# RAFT_DuckLink_3V3_Reg.net
KiCad netlist of a schematic drawn in EAGLE
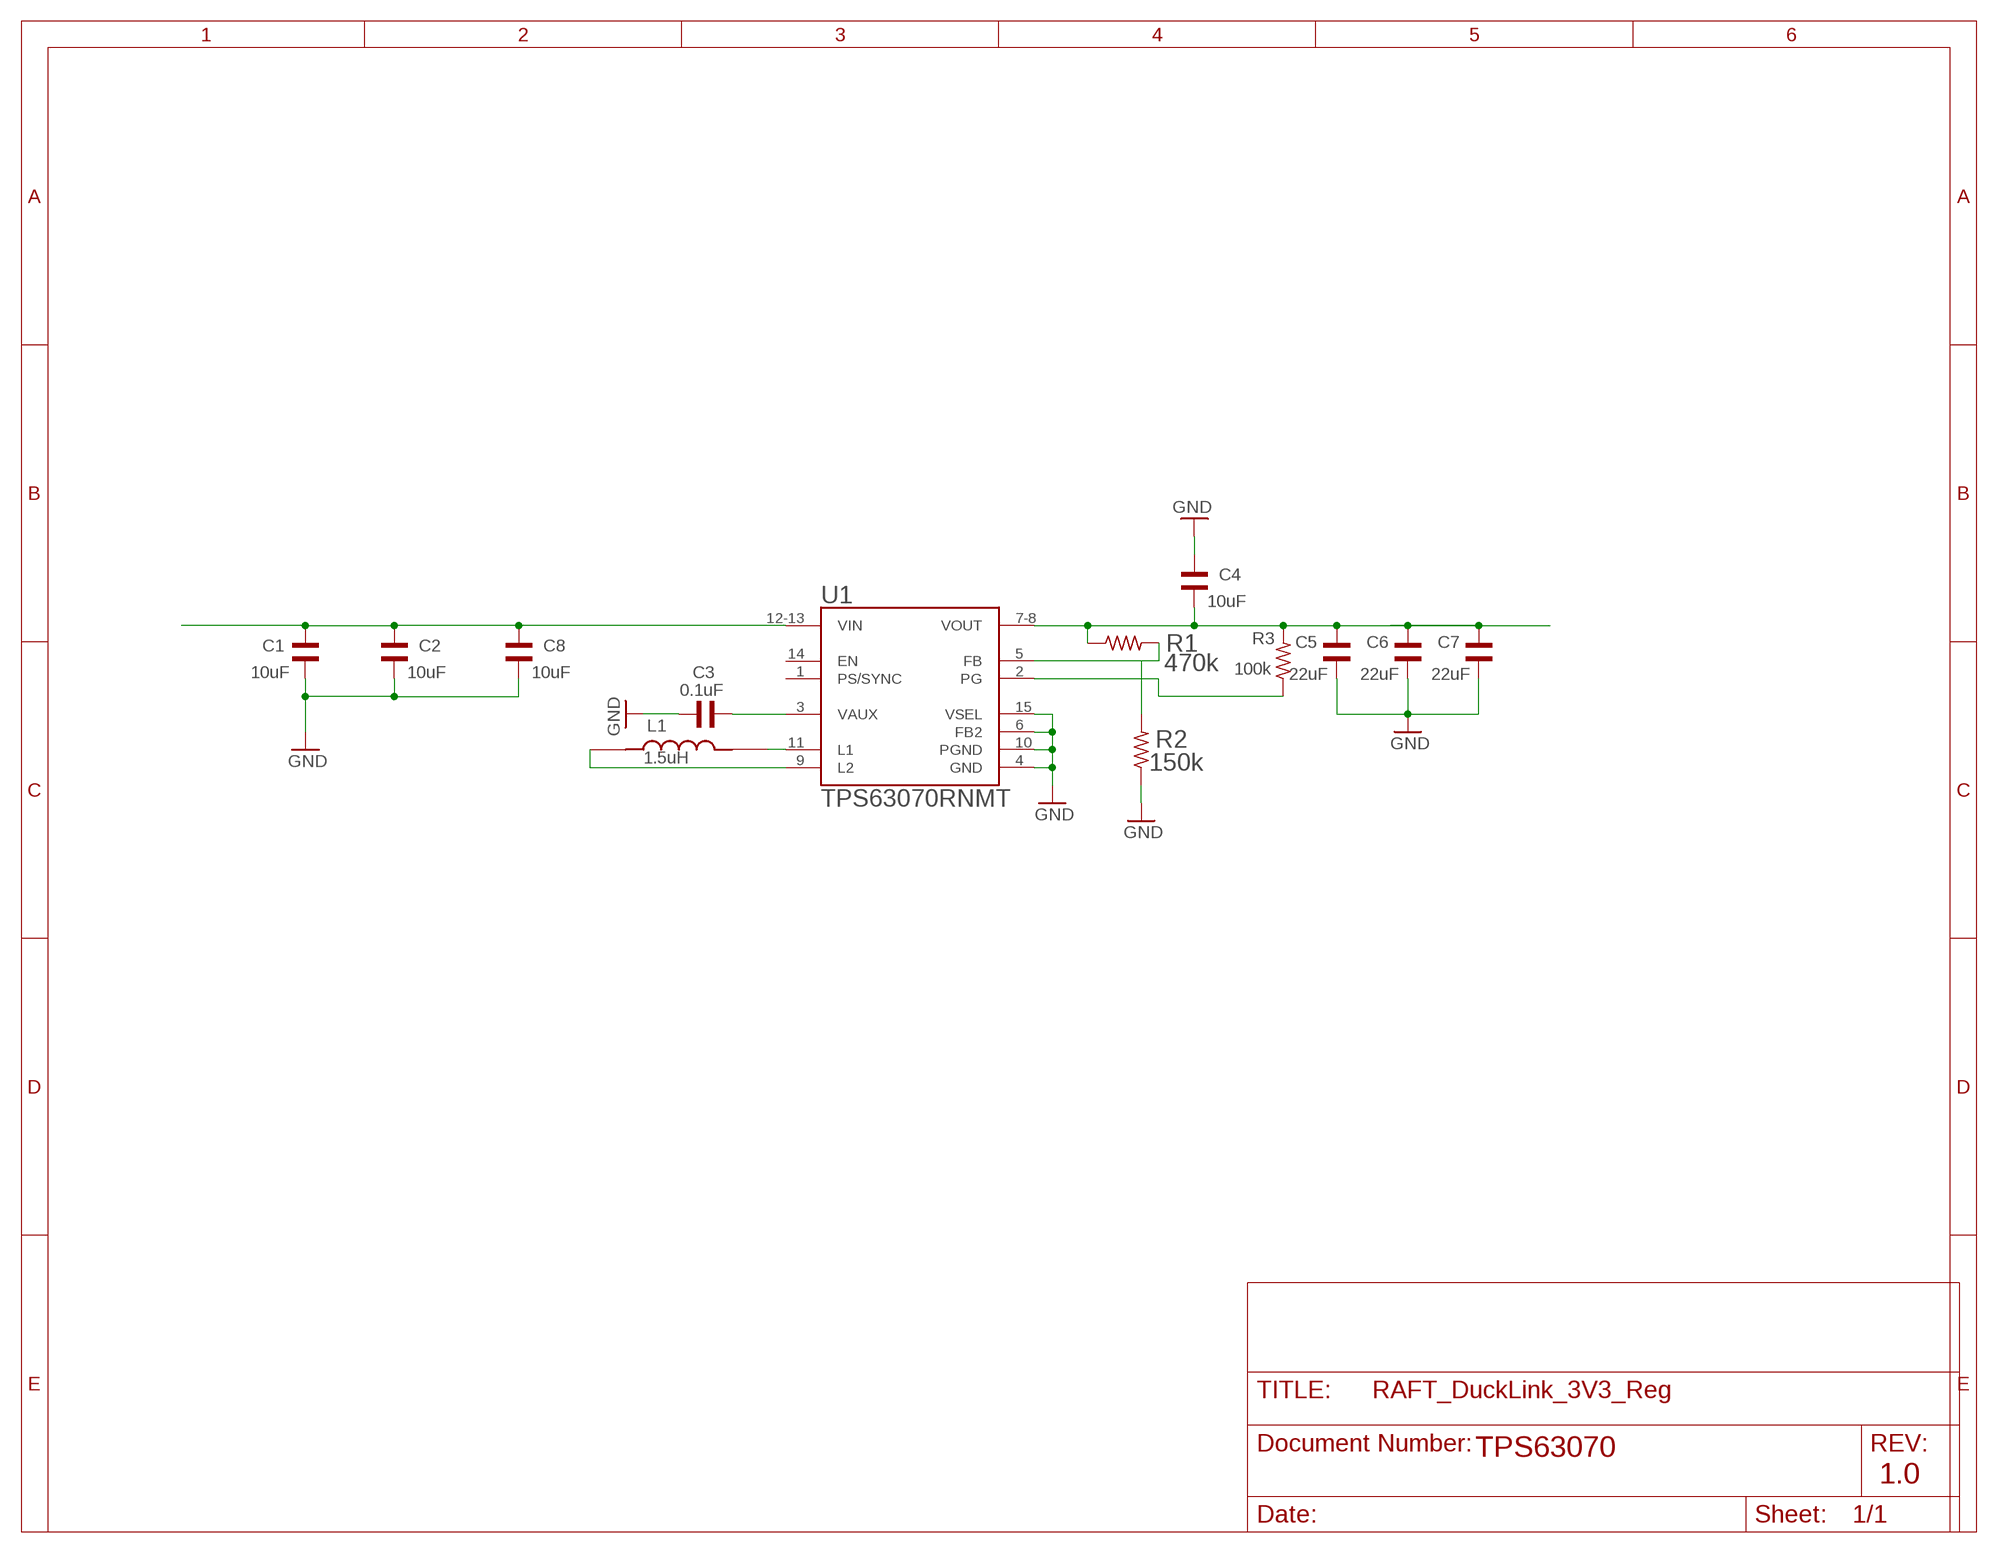
[diagram p0: schematic, sheet 1]

(export (version "E")
  (design (tool "Eeschema 10.0.6"))
  (components
    (comp (ref "C1")
      (value "10uF")
      (footprint "eagle-import:CAPC1005X70N")
      (fields (field (name "MF") "Murata Electronics") (field (name "MP") "GRM155C80J106ME11D"))
      (libsource (lib "eagle-import") (part "GRM155C80J106ME11D"))
    )
    (comp (ref "C2")
      (value "10uF")
      (footprint "eagle-import:CAPC1005X70N")
      (fields (field (name "MF") "Murata Electronics") (field (name "MP") "GRM155C80J106ME11D"))
      (libsource (lib "eagle-import") (part "GRM155C80J106ME11D"))
    )
    (comp (ref "C3")
      (value "0.1uF")
      (footprint "eagle-import:CAPC1005X55N")
      (fields (field (name "MF") "Murata") (field (name "MP") "GRM155R71C104KA88D"))
      (libsource (lib "eagle-import") (part "GRM155R71C104KA88D"))
    )
    (comp (ref "C4")
      (value "10uF")
      (footprint "eagle-import:CAPC1005X70N")
      (fields (field (name "MF") "Murata Electronics") (field (name "MP") "GRM155C80J106ME11D"))
      (libsource (lib "eagle-import") (part "GRM155C80J106ME11D"))
    )
    (comp (ref "C5")
      (value "22uF")
      (footprint "eagle-import:CAPC1005X55N")
      (fields
        (field (name "DIGI-KEY_PART_NUMBER") "1276-7090-1-ND")
        (field (name "MF") "Samsung Electro-Mechanics")
        (field (name "MP") "CL05A226MQ5N6J8")
      )
      (libsource (lib "eagle-import") (part "CL05A226MQ5N6J8"))
    )
    (comp (ref "C6")
      (value "22uF")
      (footprint "eagle-import:CAPC1005X55N")
      (fields
        (field (name "DIGI-KEY_PART_NUMBER") "1276-7090-1-ND")
        (field (name "MF") "Samsung Electro-Mechanics")
        (field (name "MP") "CL05A226MQ5N6J8")
      )
      (libsource (lib "eagle-import") (part "CL05A226MQ5N6J8"))
    )
    (comp (ref "C7")
      (value "22uF")
      (footprint "eagle-import:CAPC1005X55N")
      (fields
        (field (name "DIGI-KEY_PART_NUMBER") "1276-7090-1-ND")
        (field (name "MF") "Samsung Electro-Mechanics")
        (field (name "MP") "CL05A226MQ5N6J8")
      )
      (libsource (lib "eagle-import") (part "CL05A226MQ5N6J8"))
    )
    (comp (ref "C8")
      (value "10uF")
      (footprint "eagle-import:CAPC1005X70N")
      (fields (field (name "MF") "Murata Electronics") (field (name "MP") "GRM155C80J106ME11D"))
      (libsource (lib "eagle-import") (part "GRM155C80J106ME11D"))
    )
    (comp (ref "L1")
      (value "1.5uH")
      (footprint "eagle-import:IND_XFL4020-152MEB")
      (fields (field (name "MF") "Coilcraft") (field (name "MP") "XFL4020-152MEB"))
      (libsource (lib "eagle-import") (part "XFL4020-152MEB"))
    )
    (comp (ref "R1")
      (value "470k")
      (footprint "eagle-import:RESC1005X40N")
      (fields (field (name "MF") "Panasonic") (field (name "MP") "ERJ-PA2F4703X"))
      (libsource (lib "eagle-import") (part "ERJ-PA2F4703X"))
    )
    (comp (ref "R2")
      (value "150k")
      (footprint "eagle-import:RESC1005X40N")
      (fields (field (name "MF") "Panasonic Electronic") (field (name "MP") "ERJ-2GEJ154X"))
      (libsource (lib "eagle-import") (part "ERJ-2GEJ154X"))
    )
    (comp (ref "R3")
      (value "100k")
      (footprint "eagle-import:RESC1005X40N")
      (libsource (lib "eagle-import") (part "CRCW0402100KFKED"))
    )
    (comp (ref "U1")
      (value "TPS63070RNMT")
      (footprint "eagle-import:QFN50P250X300X100-15N")
      (fields (field (name "MF") "Texas Instruments"))
      (libsource (lib "eagle-import") (part "TPS63070RNMT"))
    )
  )
  (nets
    (net (code "1") (name "GND") (class "Default")
      (node (ref "C1") (pin "1") (pinfunction "1_1") (pintype "passive"))
      (node (ref "C2") (pin "1") (pinfunction "1_1") (pintype "passive"))
      (node (ref "C3") (pin "1") (pinfunction "1_1") (pintype "passive"))
      (node (ref "C4") (pin "2") (pinfunction "2_2") (pintype "passive"))
      (node (ref "C5") (pin "1") (pinfunction "1_1") (pintype "passive"))
      (node (ref "C6") (pin "1") (pinfunction "1_1") (pintype "passive"))
      (node (ref "C7") (pin "1") (pinfunction "1_1") (pintype "passive"))
      (node (ref "C8") (pin "1") (pinfunction "1_1") (pintype "passive"))
      (node (ref "R2") (pin "1") (pinfunction "1_1") (pintype "passive"))
      (node (ref "U1") (pin "10") (pinfunction "PGND_10") (pintype "power_in"))
      (node (ref "U1") (pin "15") (pinfunction "VSEL_15") (pintype "input"))
      (node (ref "U1") (pin "4") (pinfunction "GND_4") (pintype "power_in"))
      (node (ref "U1") (pin "6") (pinfunction "FB2_6") (pintype "output"))
    )
    (net (code "2") (name "Net-(U1-FB)") (class "Default")
      (node (ref "R1") (pin "2") (pinfunction "2_2") (pintype "passive"))
      (node (ref "R2") (pin "2") (pinfunction "2_2") (pintype "passive"))
      (node (ref "U1") (pin "5") (pinfunction "FB_5") (pintype "input"))
    )
    (net (code "3") (name "Net-(U1-L1)") (class "Default")
      (node (ref "L1") (pin "2") (pinfunction "2_2") (pintype "passive"))
      (node (ref "U1") (pin "11") (pinfunction "L1_11") (pintype "input"))
    )
    (net (code "4") (name "Net-(U1-L2)") (class "Default")
      (node (ref "L1") (pin "1") (pinfunction "1_1") (pintype "passive"))
      (node (ref "U1") (pin "9") (pinfunction "L2_9") (pintype "input"))
    )
    (net (code "5") (name "Net-(U1-PG)") (class "Default")
      (node (ref "R3") (pin "1") (pinfunction "1_1") (pintype "passive"))
      (node (ref "U1") (pin "2") (pinfunction "PG_2") (pintype "output"))
    )
    (net (code "6") (name "Net-(U1-VAUX)") (class "Default")
      (node (ref "C3") (pin "2") (pinfunction "2_2") (pintype "passive"))
      (node (ref "U1") (pin "3") (pinfunction "VAUX_3") (pintype "output"))
    )
    (net (code "7") (name "Net-(U1-VIN)") (class "Default")
      (node (ref "C1") (pin "2") (pinfunction "2_2") (pintype "passive"))
      (node (ref "C2") (pin "2") (pinfunction "2_2") (pintype "passive"))
      (node (ref "C8") (pin "2") (pinfunction "2_2") (pintype "passive"))
      (node (ref "U1") (pin "12-13") (pinfunction "VIN_12-13") (pintype "input"))
    )
    (net (code "8") (name "Net-(U1-VOUT)") (class "Default")
      (node (ref "C4") (pin "1") (pinfunction "1_1") (pintype "passive"))
      (node (ref "C5") (pin "2") (pinfunction "2_2") (pintype "passive"))
      (node (ref "C6") (pin "2") (pinfunction "2_2") (pintype "passive"))
      (node (ref "C7") (pin "2") (pinfunction "2_2") (pintype "passive"))
      (node (ref "R1") (pin "1") (pinfunction "1_1") (pintype "passive"))
      (node (ref "R3") (pin "2") (pinfunction "2_2") (pintype "passive"))
      (node (ref "U1") (pin "7-8") (pinfunction "VOUT_7-8") (pintype "output"))
    )
    (net (code "9") (name "unconnected-(U1-EN-Pad14)") (class "Default")
      (node (ref "U1") (pin "14") (pinfunction "EN_14") (pintype "input"))
    )
    (net (code "10") (name "unconnected-(U1-PS{slash}SYNC-Pad1)") (class "Default")
      (node (ref "U1") (pin "1") (pinfunction "PS/SYNC_1") (pintype "input"))
    )
  )
)
